# TSOC_GROVEY_ONE.net
KiCad netlist of a schematic drawn in EAGLE
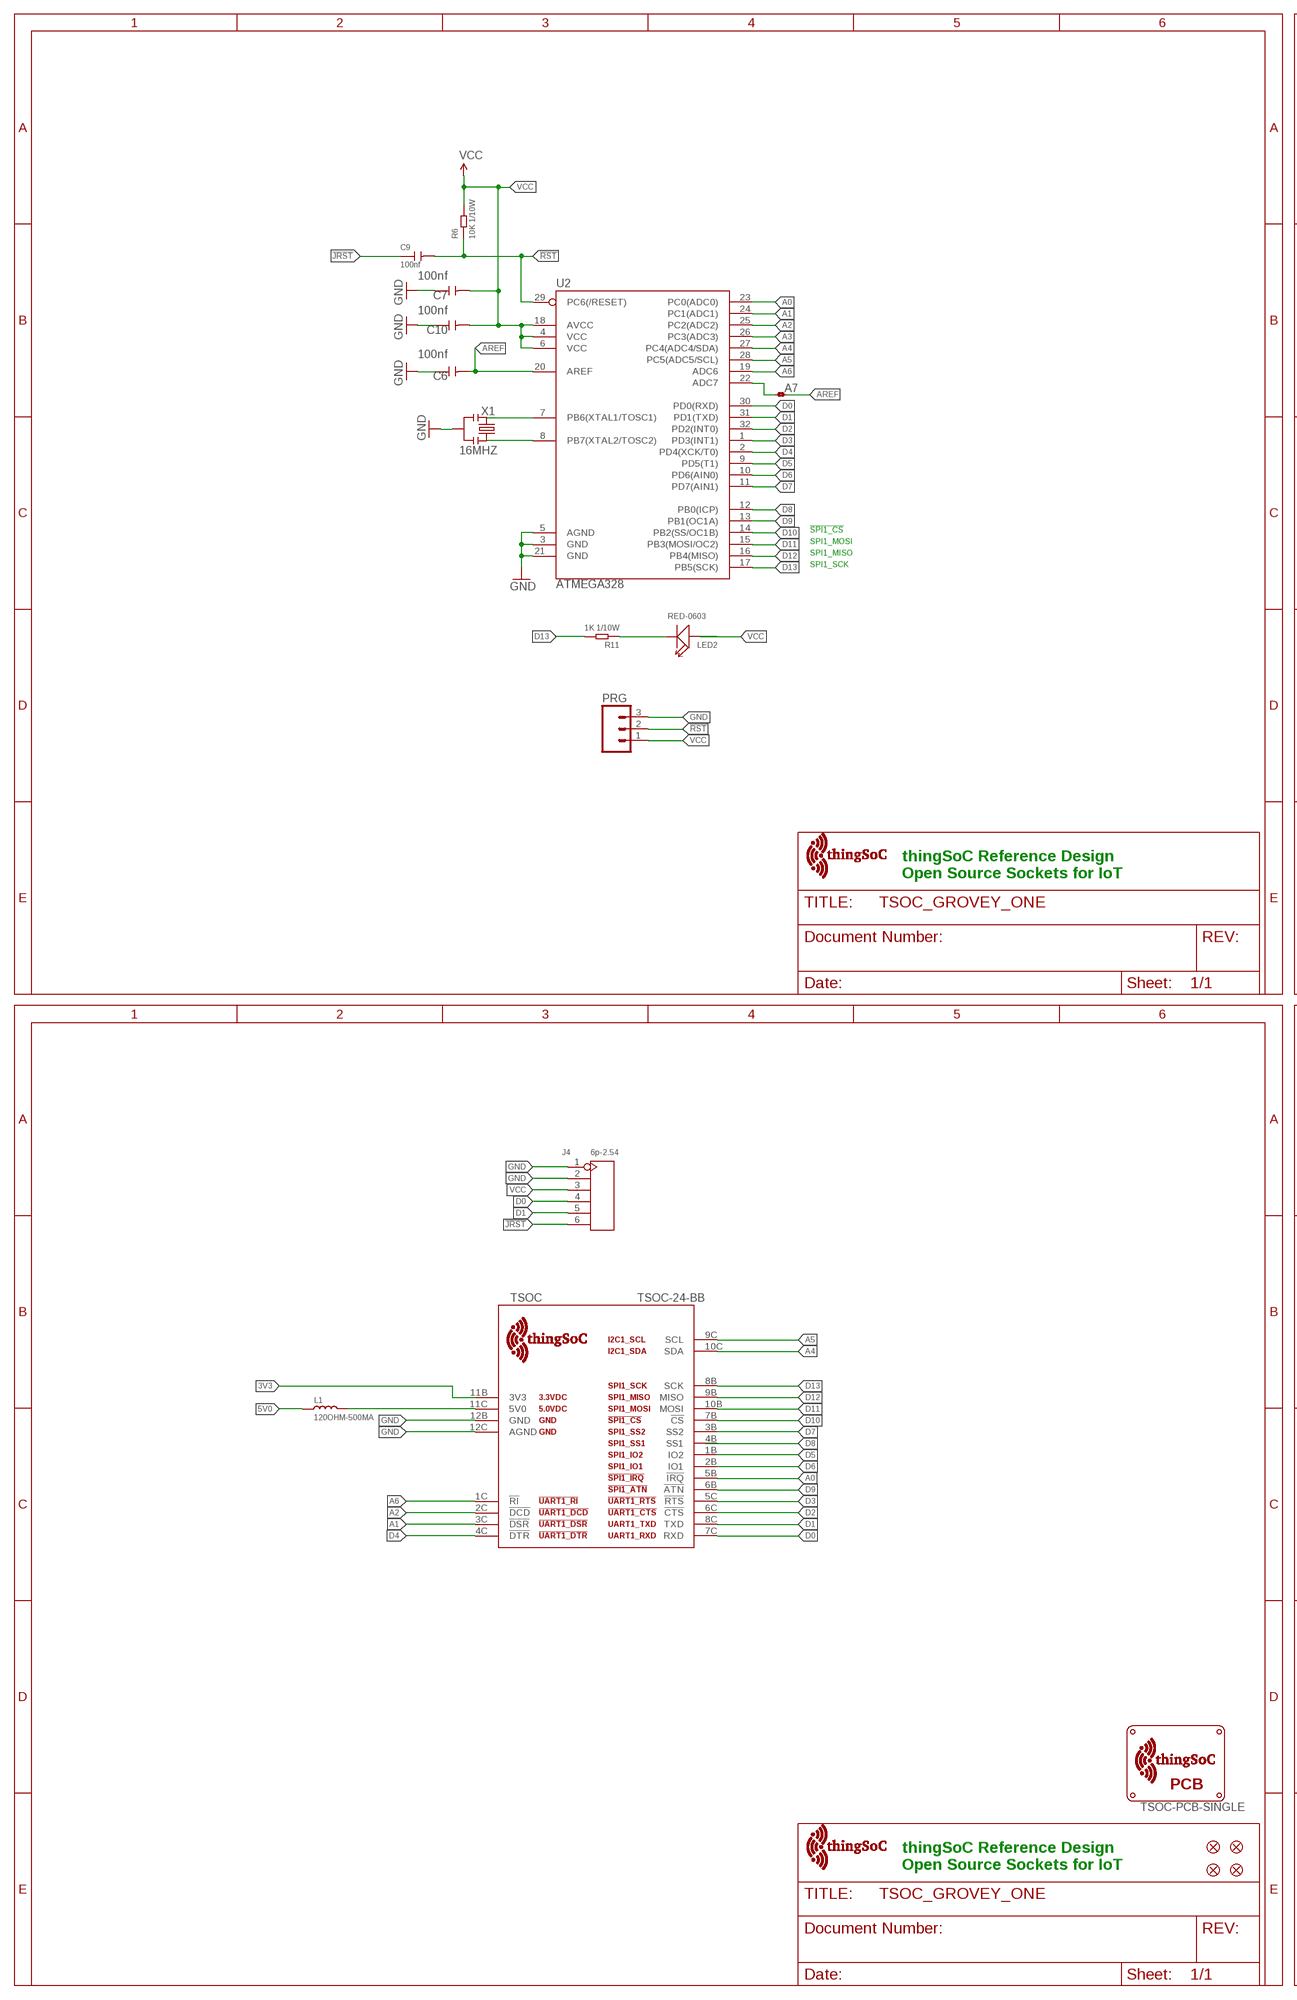
[diagram p0: schematic, sheet 1, part 1 of 2]
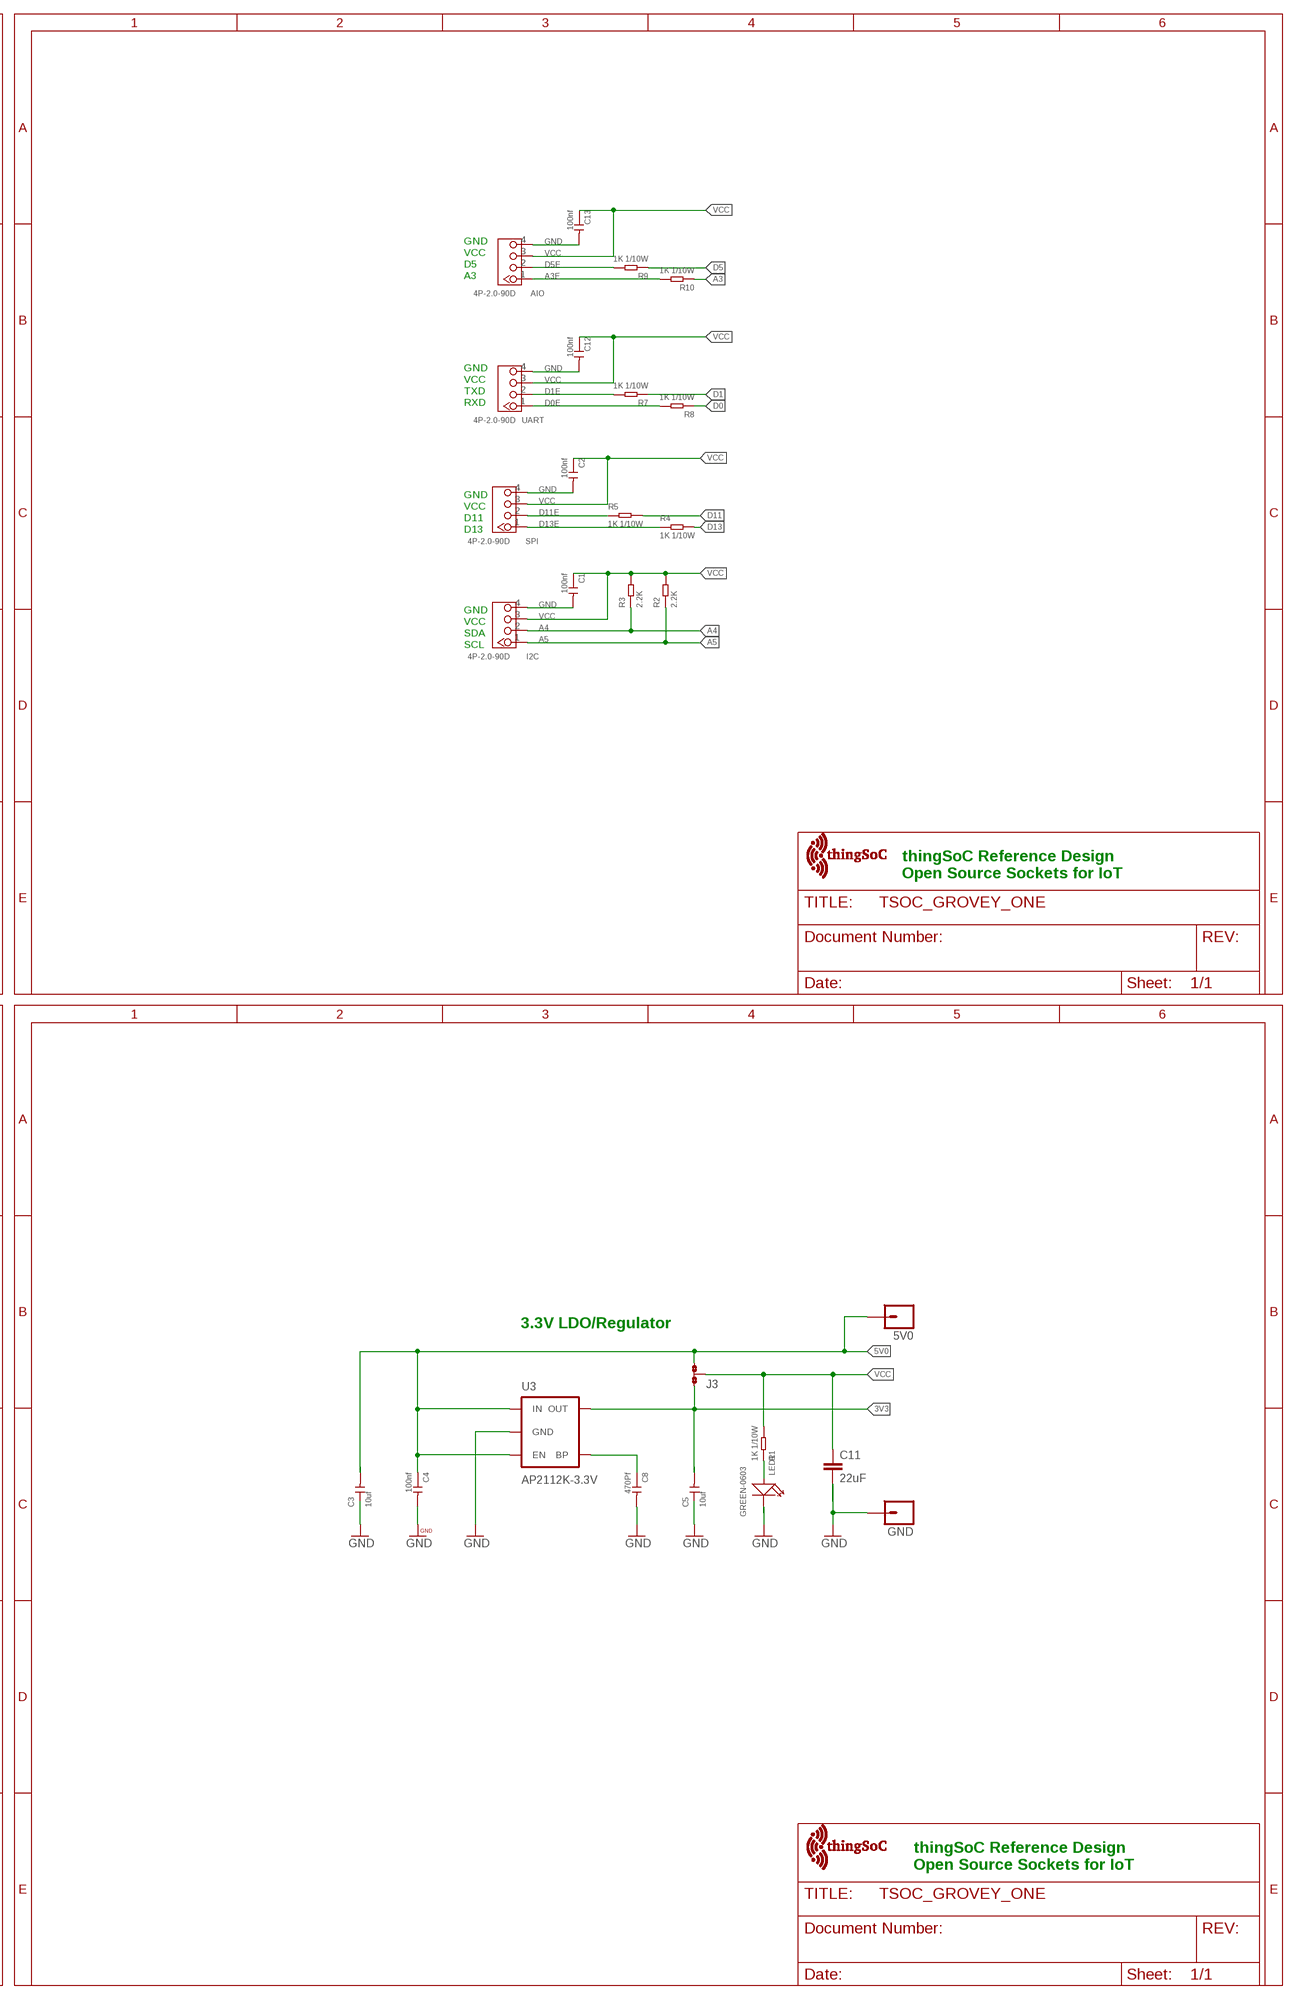
[diagram p1: schematic, sheet 1, part 2 of 2]

(export (version "E")
  (design (tool "Eeschema 10.0.6"))
  (components
    (comp (ref "$$U$1")
      (value "TSOC-PCB-SINGLE")
      (footprint "eagle-import:TSOC-BB-BRD-DIM")
      (libsource (lib "eagle-import") (part "TSOC-PCB-SINGLE"))
    )
    (comp (ref "5V0")
      (value "M01PTH")
      (footprint "eagle-import:1X01")
      (libsource (lib "eagle-import") (part "M01PTH"))
    )
    (comp (ref "A7")
      (value "JMP-2-NO")
      (footprint "eagle-import:JMP-2-NO")
      (libsource (lib "eagle-import") (part "JMP-2-NO"))
    )
    (comp (ref "AIO")
      (value "4P-2.0-90D")
      (footprint "eagle-import:HW4-2.0-90D")
      (libsource (lib "eagle-import") (part "GROVE-CONNECTOR-DIP-90D(4P-2.0)"))
    )
    (comp (ref "C1")
      (value "100nf")
      (footprint "eagle-import:C0603")
      (fields (field (name "MPN") "CC0603KRX7R9BB104"))
      (libsource (lib "eagle-import") (part "CERAMIC-100NF-50V-10%-X7R(0603)"))
    )
    (comp (ref "C2")
      (value "100nf")
      (footprint "eagle-import:C0603")
      (fields (field (name "MPN") "CC0603KRX7R9BB104"))
      (libsource (lib "eagle-import") (part "CERAMIC-100NF-50V-10%-X7R(0603)"))
    )
    (comp (ref "C3")
      (value "10uf")
      (footprint "eagle-import:C0603")
      (fields (field (name "MPN") "CC0603KRX5R6BB106"))
      (libsource (lib "eagle-import") (part "CERAMIC-10UF-10V-10%-X5R(0603)"))
    )
    (comp (ref "C4")
      (value "100nf")
      (footprint "eagle-import:C0603")
      (fields (field (name "MPN") "CC0603KRX7R9BB104"))
      (libsource (lib "eagle-import") (part "CERAMIC-100NF-50V-10%-X7R(0603)"))
    )
    (comp (ref "C5")
      (value "10uf")
      (footprint "eagle-import:C0603")
      (fields (field (name "MPN") "CC0603KRX5R6BB106"))
      (libsource (lib "eagle-import") (part "CERAMIC-10UF-10V-10%-X5R(0603)"))
    )
    (comp (ref "C6")
      (value "100nf")
      (footprint "eagle-import:C0603")
      (fields (field (name "MPN") "CC0603KRX7R9BB104"))
      (libsource (lib "eagle-import") (part "CERAMIC-100NF-50V-10%-X7R(0603)"))
    )
    (comp (ref "C7")
      (value "100nf")
      (footprint "eagle-import:C0603")
      (fields (field (name "MPN") "CC0603KRX7R9BB104"))
      (libsource (lib "eagle-import") (part "CERAMIC-100NF-50V-10%-X7R(0603)"))
    )
    (comp (ref "C8")
      (value "470Pf")
      (footprint "eagle-import:C0603")
      (fields (field (name "MPN") "CC0603KRX7R9BB104"))
      (libsource (lib "eagle-import") (part "CERAMIC-100NF-50V-10%-X7R(0603)"))
    )
    (comp (ref "C9")
      (value "100nf")
      (footprint "eagle-import:C0603")
      (fields (field (name "MPN") "CC0603KRX7R9BB104"))
      (libsource (lib "eagle-import") (part "CERAMIC-100NF-50V-10%-X7R(0603)"))
    )
    (comp (ref "C10")
      (value "100nf")
      (footprint "eagle-import:C0603")
      (fields (field (name "MPN") "CC0603KRX7R9BB104"))
      (libsource (lib "eagle-import") (part "CERAMIC-100NF-50V-10%-X7R(0603)"))
    )
    (comp (ref "C11")
      (value "22uF")
      (footprint "eagle-import:EIA-1206")
      (libsource (lib "eagle-import") (part "CAP-1206"))
    )
    (comp (ref "C12")
      (value "100nf")
      (footprint "eagle-import:C0603")
      (fields (field (name "MPN") "CC0603KRX7R9BB104"))
      (libsource (lib "eagle-import") (part "CERAMIC-100NF-50V-10%-X7R(0603)"))
    )
    (comp (ref "C13")
      (value "100nf")
      (footprint "eagle-import:C0603")
      (fields (field (name "MPN") "CC0603KRX7R9BB104"))
      (libsource (lib "eagle-import") (part "CERAMIC-100NF-50V-10%-X7R(0603)"))
    )
    (comp (ref "FID1")
      (value "FIDUCIALUFIDUCIAL")
      (footprint "eagle-import:MICRO-FIDUCIAL")
      (libsource (lib "eagle-import") (part "FIDUCIALUFIDUCIAL"))
    )
    (comp (ref "FID2")
      (value "FIDUCIALUFIDUCIAL")
      (footprint "eagle-import:MICRO-FIDUCIAL")
      (libsource (lib "eagle-import") (part "FIDUCIALUFIDUCIAL"))
    )
    (comp (ref "FID3")
      (value "FIDUCIALUFIDUCIAL")
      (footprint "eagle-import:MICRO-FIDUCIAL")
      (libsource (lib "eagle-import") (part "FIDUCIALUFIDUCIAL"))
    )
    (comp (ref "FID4")
      (value "FIDUCIALUFIDUCIAL")
      (footprint "eagle-import:MICRO-FIDUCIAL")
      (libsource (lib "eagle-import") (part "FIDUCIALUFIDUCIAL"))
    )
    (comp (ref "GND")
      (value "M01PTH")
      (footprint "eagle-import:1X01")
      (libsource (lib "eagle-import") (part "M01PTH"))
    )
    (comp (ref "I2C")
      (value "4P-2.0-90D")
      (footprint "eagle-import:HW4-2.0-90D")
      (libsource (lib "eagle-import") (part "GROVE-CONNECTOR-DIP-90D(4P-2.0)"))
    )
    (comp (ref "J3")
      (value "NO")
      (footprint "eagle-import:JMP-3-NO-PTH-2.54")
      (libsource (lib "eagle-import") (part "JMP-3-NO-PTH"))
    )
    (comp (ref "J4")
      (value "6p-2.54")
      (footprint "eagle-import:H6-2.54")
      (fields (field (name "MPN") "P125-1106A1BS116A1"))
      (libsource (lib "eagle-import") (part "DIP-BLACK-MALE-HEADER(6P-2.54)"))
    )
    (comp (ref "L1")
      (value "120OHM-500MA")
      (footprint "eagle-import:L0603")
      (fields (field (name "MPN") "BLM18AG121SN1D"))
      (libsource (lib "eagle-import") (part "SMD-FERRITE-CHIP-120-OHM-500MA(0603)"))
    )
    (comp (ref "LED1")
      (value "GREEN-0603")
      (footprint "eagle-import:LED-0603")
      (fields (field (name "MPN") "19-217-G7C-AN1P2-3T"))
      (libsource (lib "eagle-import") (part "SMD-LED-CLEAR-GREEN(0603)"))
    )
    (comp (ref "LED2")
      (value "RED-0603")
      (footprint "eagle-import:LED-0603")
      (fields (field (name "MPN") "19-217-G7C-AN1P2-3T"))
      (libsource (lib "eagle-import") (part "SMD-LED-CLEAR-GREEN(0603)"))
    )
    (comp (ref "PRG")
      (value "M03PTH")
      (footprint "eagle-import:1X03")
      (libsource (lib "eagle-import") (part "M03PTH"))
    )
    (comp (ref "R1")
      (value "1K 1/10W")
      (footprint "eagle-import:R0603")
      (fields (field (name "MPN") "RC0603JR-071KL"))
      (libsource (lib "eagle-import") (part "SMD-RES-1K-5%-1/10W(0603)"))
    )
    (comp (ref "R2")
      (value "2.2K")
      (footprint "eagle-import:R0603")
      (fields (field (name "MPN") "RC0603JR-072K2L"))
      (libsource (lib "eagle-import") (part "SMD-RES-2.2K-5%-1/10W(0603)"))
    )
    (comp (ref "R3")
      (value "2.2K")
      (footprint "eagle-import:R0603")
      (fields (field (name "MPN") "RC0603JR-072K2L"))
      (libsource (lib "eagle-import") (part "SMD-RES-2.2K-5%-1/10W(0603)"))
    )
    (comp (ref "R4")
      (value "1K 1/10W")
      (footprint "eagle-import:R0603")
      (fields (field (name "MPN") "RC0603JR-071KL"))
      (libsource (lib "eagle-import") (part "SMD-RES-1K-5%-1/10W(0603)"))
    )
    (comp (ref "R5")
      (value "1K 1/10W")
      (footprint "eagle-import:R0603")
      (fields (field (name "MPN") "RC0603JR-071KL"))
      (libsource (lib "eagle-import") (part "SMD-RES-1K-5%-1/10W(0603)"))
    )
    (comp (ref "R6")
      (value "10K 1/10W")
      (footprint "eagle-import:R0603")
      (fields (field (name "MPN") "RC0603JR-0710KL"))
      (libsource (lib "eagle-import") (part "SMD-RES-10K-5%-1/10W(0603)"))
    )
    (comp (ref "R7")
      (value "1K 1/10W")
      (footprint "eagle-import:R0603")
      (fields (field (name "MPN") "RC0603JR-071KL"))
      (libsource (lib "eagle-import") (part "SMD-RES-1K-5%-1/10W(0603)"))
    )
    (comp (ref "R8")
      (value "1K 1/10W")
      (footprint "eagle-import:R0603")
      (fields (field (name "MPN") "RC0603JR-071KL"))
      (libsource (lib "eagle-import") (part "SMD-RES-1K-5%-1/10W(0603)"))
    )
    (comp (ref "R9")
      (value "1K 1/10W")
      (footprint "eagle-import:R0603")
      (fields (field (name "MPN") "RC0603JR-071KL"))
      (libsource (lib "eagle-import") (part "SMD-RES-1K-5%-1/10W(0603)"))
    )
    (comp (ref "R10")
      (value "1K 1/10W")
      (footprint "eagle-import:R0603")
      (fields (field (name "MPN") "RC0603JR-071KL"))
      (libsource (lib "eagle-import") (part "SMD-RES-1K-5%-1/10W(0603)"))
    )
    (comp (ref "R11")
      (value "1K 1/10W")
      (footprint "eagle-import:R0603")
      (fields (field (name "MPN") "RC0603JR-071KL"))
      (libsource (lib "eagle-import") (part "SMD-RES-1K-5%-1/10W(0603)"))
    )
    (comp (ref "SPI")
      (value "4P-2.0-90D")
      (footprint "eagle-import:HW4-2.0-90D")
      (libsource (lib "eagle-import") (part "GROVE-CONNECTOR-DIP-90D(4P-2.0)"))
    )
    (comp (ref "TSOC")
      (value "TSOC-24-BB")
      (footprint "eagle-import:TSOC-BB-S24")
      (libsource (lib "eagle-import") (part "TSOC-24-BB"))
    )
    (comp (ref "U$1")
      (value "TSOC-LOGO-SMALL")
      (footprint "eagle-import:TSOC-LOGO-SML")
      (libsource (lib "eagle-import") (part "TSOC-LOGO-SMALL"))
    )
    (comp (ref "U$101")
      (value "TSOC-LOGO-SMALL")
      (footprint "eagle-import:TSOC-LOGO-SML")
      (libsource (lib "eagle-import") (part "TSOC-LOGO-SMALL"))
    )
    (comp (ref "U$102")
      (value "TSOC-LOGO-LRG")
      (footprint "eagle-import:TSOC-LOGO-LRG")
      (libsource (lib "eagle-import") (part "TSOC-LOGO-LRG"))
    )
    (comp (ref "U$103")
      (value "TSOC-LOGO-SMALL")
      (footprint "eagle-import:TSOC-LOGO-SML")
      (libsource (lib "eagle-import") (part "TSOC-LOGO-SMALL"))
    )
    (comp (ref "U2")
      (value "ATMEGA328")
      (footprint "eagle-import:TQFP32-08")
      (libsource (lib "eagle-import") (part "ATMEGA168"))
    )
    (comp (ref "U3")
      (value "AP2112K-3.3V")
      (footprint "eagle-import:SOT23-5")
      (libsource (lib "eagle-import") (part "V_REG_LDOSMD"))
    )
    (comp (ref "UART")
      (value "4P-2.0-90D")
      (footprint "eagle-import:HW4-2.0-90D")
      (libsource (lib "eagle-import") (part "GROVE-CONNECTOR-DIP-90D(4P-2.0)"))
    )
    (comp (ref "X1")
      (value "16MHZ")
      (footprint "eagle-import:X3-SMD-3.6X1.3X0.8MM")
      (fields (field (name "MPN") "CSTCE16M0V53-R0"))
      (libsource (lib "eagle-import") (part "SMD-RESONATOR-16MHZ-15PF-0.5%-40R(3P-3.2X1.3MM)"))
    )
  )
  (nets
    (net (code "1") (name "/A3E") (class "Default")
      (node (ref "AIO") (pin "1") (pinfunction "1_1") (pintype "bidirectional"))
      (node (ref "R10") (pin "2") (pinfunction "2_2") (pintype "passive"))
    )
    (net (code "2") (name "/D0E") (class "Default")
      (node (ref "R8") (pin "2") (pinfunction "2_2") (pintype "passive"))
      (node (ref "UART") (pin "1") (pinfunction "1_1") (pintype "bidirectional"))
    )
    (net (code "3") (name "/D1E") (class "Default")
      (node (ref "R7") (pin "2") (pinfunction "2_2") (pintype "passive"))
      (node (ref "UART") (pin "2") (pinfunction "2_2") (pintype "bidirectional"))
    )
    (net (code "4") (name "/D5E") (class "Default")
      (node (ref "AIO") (pin "2") (pinfunction "2_2") (pintype "bidirectional"))
      (node (ref "R9") (pin "2") (pinfunction "2_2") (pintype "passive"))
    )
    (net (code "5") (name "/D11E") (class "Default")
      (node (ref "R5") (pin "1") (pinfunction "1_1") (pintype "passive"))
      (node (ref "SPI") (pin "2") (pinfunction "2_2") (pintype "bidirectional"))
    )
    (net (code "6") (name "/D13E") (class "Default")
      (node (ref "R4") (pin "1") (pinfunction "1_1") (pintype "passive"))
      (node (ref "SPI") (pin "1") (pinfunction "1_1") (pintype "bidirectional"))
    )
    (net (code "7") (name "/~{JRST}") (class "Default")
      (node (ref "C9") (pin "1") (pinfunction "1_1") (pintype "passive"))
      (node (ref "J4") (pin "6") (pinfunction "6_6") (pintype "bidirectional"))
    )
    (net (code "8") (name "/~{RST}") (class "Default")
      (node (ref "C9") (pin "2") (pinfunction "2_2") (pintype "passive"))
      (node (ref "PRG") (pin "2") (pinfunction "2_2") (pintype "passive"))
      (node (ref "R6") (pin "1") (pinfunction "1_1") (pintype "passive"))
      (node (ref "U2") (pin "29") (pinfunction "PC6(/RESET)_29") (pintype "bidirectional"))
    )
    (net (code "9") (name "3V3") (class "Default")
      (node (ref "C5") (pin "2") (pinfunction "2_2") (pintype "passive"))
      (node (ref "J3") (pin "1") (pinfunction "1_1") (pintype "passive"))
      (node (ref "TSOC") (pin "11B") (pinfunction "3V3_11B") (pintype "bidirectional"))
      (node (ref "U3") (pin "5") (pinfunction "OUT_5") (pintype "passive"))
    )
    (net (code "10") (name "5V0") (class "Default")
      (node (ref "5V0") (pin "1") (pinfunction "1_1") (pintype "passive"))
      (node (ref "C3") (pin "2") (pinfunction "2_2") (pintype "passive"))
      (node (ref "C4") (pin "1") (pinfunction "1_1") (pintype "passive"))
      (node (ref "J3") (pin "3") (pinfunction "3_3") (pintype "passive"))
      (node (ref "L1") (pin "1") (pinfunction "1_1") (pintype "passive"))
      (node (ref "U3") (pin "1") (pinfunction "IN_1") (pintype "input"))
      (node (ref "U3") (pin "3") (pinfunction "EN_3") (pintype "input"))
    )
    (net (code "11") (name "A0") (class "Default")
      (node (ref "TSOC") (pin "5B") (pinfunction "~{IRQ}_5B") (pintype "bidirectional"))
      (node (ref "U2") (pin "23") (pinfunction "PC0(ADC0)_23") (pintype "bidirectional"))
    )
    (net (code "12") (name "A1") (class "Default")
      (node (ref "TSOC") (pin "3C") (pinfunction "~{DSR}_3C") (pintype "bidirectional"))
      (node (ref "U2") (pin "24") (pinfunction "PC1(ADC1)_24") (pintype "bidirectional"))
    )
    (net (code "13") (name "A2") (class "Default")
      (node (ref "TSOC") (pin "2C") (pinfunction "~{DCD}_2C") (pintype "bidirectional"))
      (node (ref "U2") (pin "25") (pinfunction "PC2(ADC2)_25") (pintype "bidirectional"))
    )
    (net (code "14") (name "A3") (class "Default")
      (node (ref "R10") (pin "1") (pinfunction "1_1") (pintype "passive"))
      (node (ref "U2") (pin "26") (pinfunction "PC3(ADC3)_26") (pintype "bidirectional"))
    )
    (net (code "15") (name "A4") (class "Default")
      (node (ref "I2C") (pin "2") (pinfunction "2_2") (pintype "bidirectional"))
      (node (ref "R3") (pin "1") (pinfunction "1_1") (pintype "passive"))
      (node (ref "TSOC") (pin "10C") (pinfunction "SDA_10C") (pintype "bidirectional"))
      (node (ref "U2") (pin "27") (pinfunction "PC4(ADC4/SDA)_27") (pintype "bidirectional"))
    )
    (net (code "16") (name "A5") (class "Default")
      (node (ref "I2C") (pin "1") (pinfunction "1_1") (pintype "bidirectional"))
      (node (ref "R2") (pin "1") (pinfunction "1_1") (pintype "passive"))
      (node (ref "TSOC") (pin "9C") (pinfunction "SCL_9C") (pintype "bidirectional"))
      (node (ref "U2") (pin "28") (pinfunction "PC5(ADC5/SCL)_28") (pintype "bidirectional"))
    )
    (net (code "17") (name "A6") (class "Default")
      (node (ref "TSOC") (pin "1C") (pinfunction "~{RI}_1C") (pintype "bidirectional"))
      (node (ref "U2") (pin "19") (pinfunction "ADC6_19") (pintype "bidirectional"))
    )
    (net (code "18") (name "AREF") (class "Default")
      (node (ref "A7") (pin "2") (pinfunction "2_2") (pintype "passive"))
      (node (ref "C6") (pin "2") (pinfunction "2_2") (pintype "passive"))
      (node (ref "U2") (pin "20") (pinfunction "AREF_20") (pintype "bidirectional"))
    )
    (net (code "19") (name "D0") (class "Default")
      (node (ref "J4") (pin "4") (pinfunction "4_4") (pintype "bidirectional"))
      (node (ref "R8") (pin "1") (pinfunction "1_1") (pintype "passive"))
      (node (ref "TSOC") (pin "7C") (pinfunction "RXD_7C") (pintype "bidirectional"))
      (node (ref "U2") (pin "30") (pinfunction "PD0(RXD)_30") (pintype "bidirectional"))
    )
    (net (code "20") (name "D1") (class "Default")
      (node (ref "J4") (pin "5") (pinfunction "5_5") (pintype "bidirectional"))
      (node (ref "R7") (pin "1") (pinfunction "1_1") (pintype "passive"))
      (node (ref "TSOC") (pin "8C") (pinfunction "TXD_8C") (pintype "bidirectional"))
      (node (ref "U2") (pin "31") (pinfunction "PD1(TXD)_31") (pintype "bidirectional"))
    )
    (net (code "21") (name "D2") (class "Default")
      (node (ref "TSOC") (pin "6C") (pinfunction "~{CTS}_6C") (pintype "bidirectional"))
      (node (ref "U2") (pin "32") (pinfunction "PD2(INT0)_32") (pintype "bidirectional"))
    )
    (net (code "22") (name "D3") (class "Default")
      (node (ref "TSOC") (pin "5C") (pinfunction "~{RTS}_5C") (pintype "bidirectional"))
      (node (ref "U2") (pin "1") (pinfunction "PD3(INT1)_1") (pintype "bidirectional"))
    )
    (net (code "23") (name "D4") (class "Default")
      (node (ref "TSOC") (pin "4C") (pinfunction "~{DTR}_4C") (pintype "bidirectional"))
      (node (ref "U2") (pin "2") (pinfunction "PD4(XCK/T0)_2") (pintype "bidirectional"))
    )
    (net (code "24") (name "D5") (class "Default")
      (node (ref "R9") (pin "1") (pinfunction "1_1") (pintype "passive"))
      (node (ref "TSOC") (pin "1B") (pinfunction "IO2_1B") (pintype "bidirectional"))
      (node (ref "U2") (pin "9") (pinfunction "PD5(T1)_9") (pintype "bidirectional"))
    )
    (net (code "25") (name "D6") (class "Default")
      (node (ref "TSOC") (pin "2B") (pinfunction "IO1_2B") (pintype "bidirectional"))
      (node (ref "U2") (pin "10") (pinfunction "PD6(AIN0)_10") (pintype "bidirectional"))
    )
    (net (code "26") (name "D7") (class "Default")
      (node (ref "TSOC") (pin "3B") (pinfunction "SS2_3B") (pintype "bidirectional"))
      (node (ref "U2") (pin "11") (pinfunction "PD7(AIN1)_11") (pintype "bidirectional"))
    )
    (net (code "27") (name "D8") (class "Default")
      (node (ref "TSOC") (pin "4B") (pinfunction "SS1_4B") (pintype "bidirectional"))
      (node (ref "U2") (pin "12") (pinfunction "PB0(ICP)_12") (pintype "bidirectional"))
    )
    (net (code "28") (name "D9") (class "Default")
      (node (ref "TSOC") (pin "6B") (pinfunction "~{ATN}_6B") (pintype "bidirectional"))
      (node (ref "U2") (pin "13") (pinfunction "PB1(OC1A)_13") (pintype "bidirectional"))
    )
    (net (code "29") (name "D10") (class "Default")
      (node (ref "TSOC") (pin "7B") (pinfunction "~{CS}_7B") (pintype "bidirectional"))
      (node (ref "U2") (pin "14") (pinfunction "PB2(SS/OC1B)_14") (pintype "bidirectional"))
    )
    (net (code "30") (name "D11") (class "Default")
      (node (ref "R5") (pin "2") (pinfunction "2_2") (pintype "passive"))
      (node (ref "TSOC") (pin "10B") (pinfunction "MOSI_10B") (pintype "bidirectional"))
      (node (ref "U2") (pin "15") (pinfunction "PB3(MOSI/OC2)_15") (pintype "bidirectional"))
    )
    (net (code "31") (name "D12") (class "Default")
      (node (ref "TSOC") (pin "9B") (pinfunction "MISO_9B") (pintype "bidirectional"))
      (node (ref "U2") (pin "16") (pinfunction "PB4(MISO)_16") (pintype "bidirectional"))
    )
    (net (code "32") (name "D13") (class "Default")
      (node (ref "R11") (pin "2") (pinfunction "2_2") (pintype "passive"))
      (node (ref "R4") (pin "2") (pinfunction "2_2") (pintype "passive"))
      (node (ref "TSOC") (pin "8B") (pinfunction "SCK_8B") (pintype "bidirectional"))
      (node (ref "U2") (pin "17") (pinfunction "PB5(SCK)_17") (pintype "bidirectional"))
    )
    (net (code "33") (name "GND") (class "Default")
      (node (ref "AIO") (pin "4") (pinfunction "4_4") (pintype "bidirectional"))
      (node (ref "C1") (pin "2") (pinfunction "2_2") (pintype "passive"))
      (node (ref "C10") (pin "1") (pinfunction "1_1") (pintype "passive"))
      (node (ref "C11") (pin "2") (pinfunction "2_2") (pintype "passive"))
      (node (ref "C12") (pin "2") (pinfunction "2_2") (pintype "passive"))
      (node (ref "C13") (pin "2") (pinfunction "2_2") (pintype "passive"))
      (node (ref "C2") (pin "2") (pinfunction "2_2") (pintype "passive"))
      (node (ref "C3") (pin "1") (pinfunction "1_1") (pintype "passive"))
      (node (ref "C4") (pin "2") (pinfunction "2_2") (pintype "passive"))
      (node (ref "C5") (pin "1") (pinfunction "1_1") (pintype "passive"))
      (node (ref "C6") (pin "1") (pinfunction "1_1") (pintype "passive"))
      (node (ref "C7") (pin "1") (pinfunction "1_1") (pintype "passive"))
      (node (ref "C8") (pin "2") (pinfunction "2_2") (pintype "passive"))
      (node (ref "GND") (pin "1") (pinfunction "1_1") (pintype "passive"))
      (node (ref "I2C") (pin "4") (pinfunction "4_4") (pintype "bidirectional"))
      (node (ref "J4") (pin "1") (pinfunction "1_1") (pintype "bidirectional"))
      (node (ref "J4") (pin "2") (pinfunction "2_2") (pintype "bidirectional"))
      (node (ref "LED1") (pin "-") (pinfunction "-_-") (pintype "passive"))
      (node (ref "PRG") (pin "3") (pinfunction "3_3") (pintype "passive"))
      (node (ref "SPI") (pin "4") (pinfunction "4_4") (pintype "bidirectional"))
      (node (ref "TSOC") (pin "12B") (pinfunction "GND_12B") (pintype "bidirectional"))
      (node (ref "TSOC") (pin "12C") (pinfunction "AGND_12C") (pintype "bidirectional"))
      (node (ref "U2") (pin "21") (pinfunction "GND_21") (pintype "bidirectional"))
      (node (ref "U2") (pin "3") (pinfunction "GND_3") (pintype "bidirectional"))
      (node (ref "U2") (pin "5") (pinfunction "AGND_5") (pintype "bidirectional"))
      (node (ref "U3") (pin "2") (pinfunction "GND_2") (pintype "input"))
      (node (ref "UART") (pin "4") (pinfunction "4_4") (pintype "bidirectional"))
      (node (ref "X1") (pin "2") (pinfunction "2_2") (pintype "passive"))
    )
    (net (code "34") (name "Net-(LED1-Pad+)") (class "Default")
      (node (ref "LED1") (pin "+") (pinfunction "+_+") (pintype "passive"))
      (node (ref "R1") (pin "1") (pinfunction "1_1") (pintype "passive"))
    )
    (net (code "35") (name "Net-(LED2-Pad-)") (class "Default")
      (node (ref "LED2") (pin "-") (pinfunction "-_-") (pintype "passive"))
      (node (ref "R11") (pin "1") (pinfunction "1_1") (pintype "passive"))
    )
    (net (code "36") (name "Net-(TSOC-5V0)") (class "Default")
      (node (ref "L1") (pin "2") (pinfunction "2_2") (pintype "passive"))
      (node (ref "TSOC") (pin "11C") (pinfunction "5V0_11C") (pintype "bidirectional"))
    )
    (net (code "37") (name "Net-(U2-ADC7)") (class "Default")
      (node (ref "A7") (pin "1") (pinfunction "1_1") (pintype "passive"))
      (node (ref "U2") (pin "22") (pinfunction "ADC7_22") (pintype "bidirectional"))
    )
    (net (code "38") (name "Net-(U2-PB6(XTAL1{slash}TOSC1))") (class "Default")
      (node (ref "U2") (pin "7") (pinfunction "PB6(XTAL1/TOSC1)_7") (pintype "bidirectional"))
      (node (ref "X1") (pin "3") (pinfunction "3_3") (pintype "passive"))
    )
    (net (code "39") (name "Net-(U2-PB7(XTAL2{slash}TOSC2))") (class "Default")
      (node (ref "U2") (pin "8") (pinfunction "PB7(XTAL2/TOSC2)_8") (pintype "bidirectional"))
      (node (ref "X1") (pin "1") (pinfunction "1_1") (pintype "passive"))
    )
    (net (code "40") (name "Net-(U3-BP)") (class "Default")
      (node (ref "C8") (pin "1") (pinfunction "1_1") (pintype "passive"))
      (node (ref "U3") (pin "4") (pinfunction "BP_4") (pintype "input"))
    )
    (net (code "41") (name "VCC") (class "Default")
      (node (ref "AIO") (pin "3") (pinfunction "3_3") (pintype "bidirectional"))
      (node (ref "C1") (pin "1") (pinfunction "1_1") (pintype "passive"))
      (node (ref "C10") (pin "2") (pinfunction "2_2") (pintype "passive"))
      (node (ref "C11") (pin "1") (pinfunction "1_1") (pintype "passive"))
      (node (ref "C12") (pin "1") (pinfunction "1_1") (pintype "passive"))
      (node (ref "C13") (pin "1") (pinfunction "1_1") (pintype "passive"))
      (node (ref "C2") (pin "1") (pinfunction "1_1") (pintype "passive"))
      (node (ref "C7") (pin "2") (pinfunction "2_2") (pintype "passive"))
      (node (ref "I2C") (pin "3") (pinfunction "3_3") (pintype "bidirectional"))
      (node (ref "J3") (pin "2") (pinfunction "2_2") (pintype "passive"))
      (node (ref "J4") (pin "3") (pinfunction "3_3") (pintype "bidirectional"))
      (node (ref "LED2") (pin "+") (pinfunction "+_+") (pintype "passive"))
      (node (ref "PRG") (pin "1") (pinfunction "1_1") (pintype "passive"))
      (node (ref "R1") (pin "2") (pinfunction "2_2") (pintype "passive"))
      (node (ref "R2") (pin "2") (pinfunction "2_2") (pintype "passive"))
      (node (ref "R3") (pin "2") (pinfunction "2_2") (pintype "passive"))
      (node (ref "R6") (pin "2") (pinfunction "2_2") (pintype "passive"))
      (node (ref "SPI") (pin "3") (pinfunction "3_3") (pintype "bidirectional"))
      (node (ref "U2") (pin "18") (pinfunction "AVCC_18") (pintype "bidirectional"))
      (node (ref "U2") (pin "4") (pinfunction "VCC_4") (pintype "bidirectional"))
      (node (ref "U2") (pin "6") (pinfunction "VCC_6") (pintype "bidirectional"))
      (node (ref "UART") (pin "3") (pinfunction "3_3") (pintype "bidirectional"))
    )
  )
)
